# SFP.net
KiCad netlist of a schematic drawn in Altium Designer
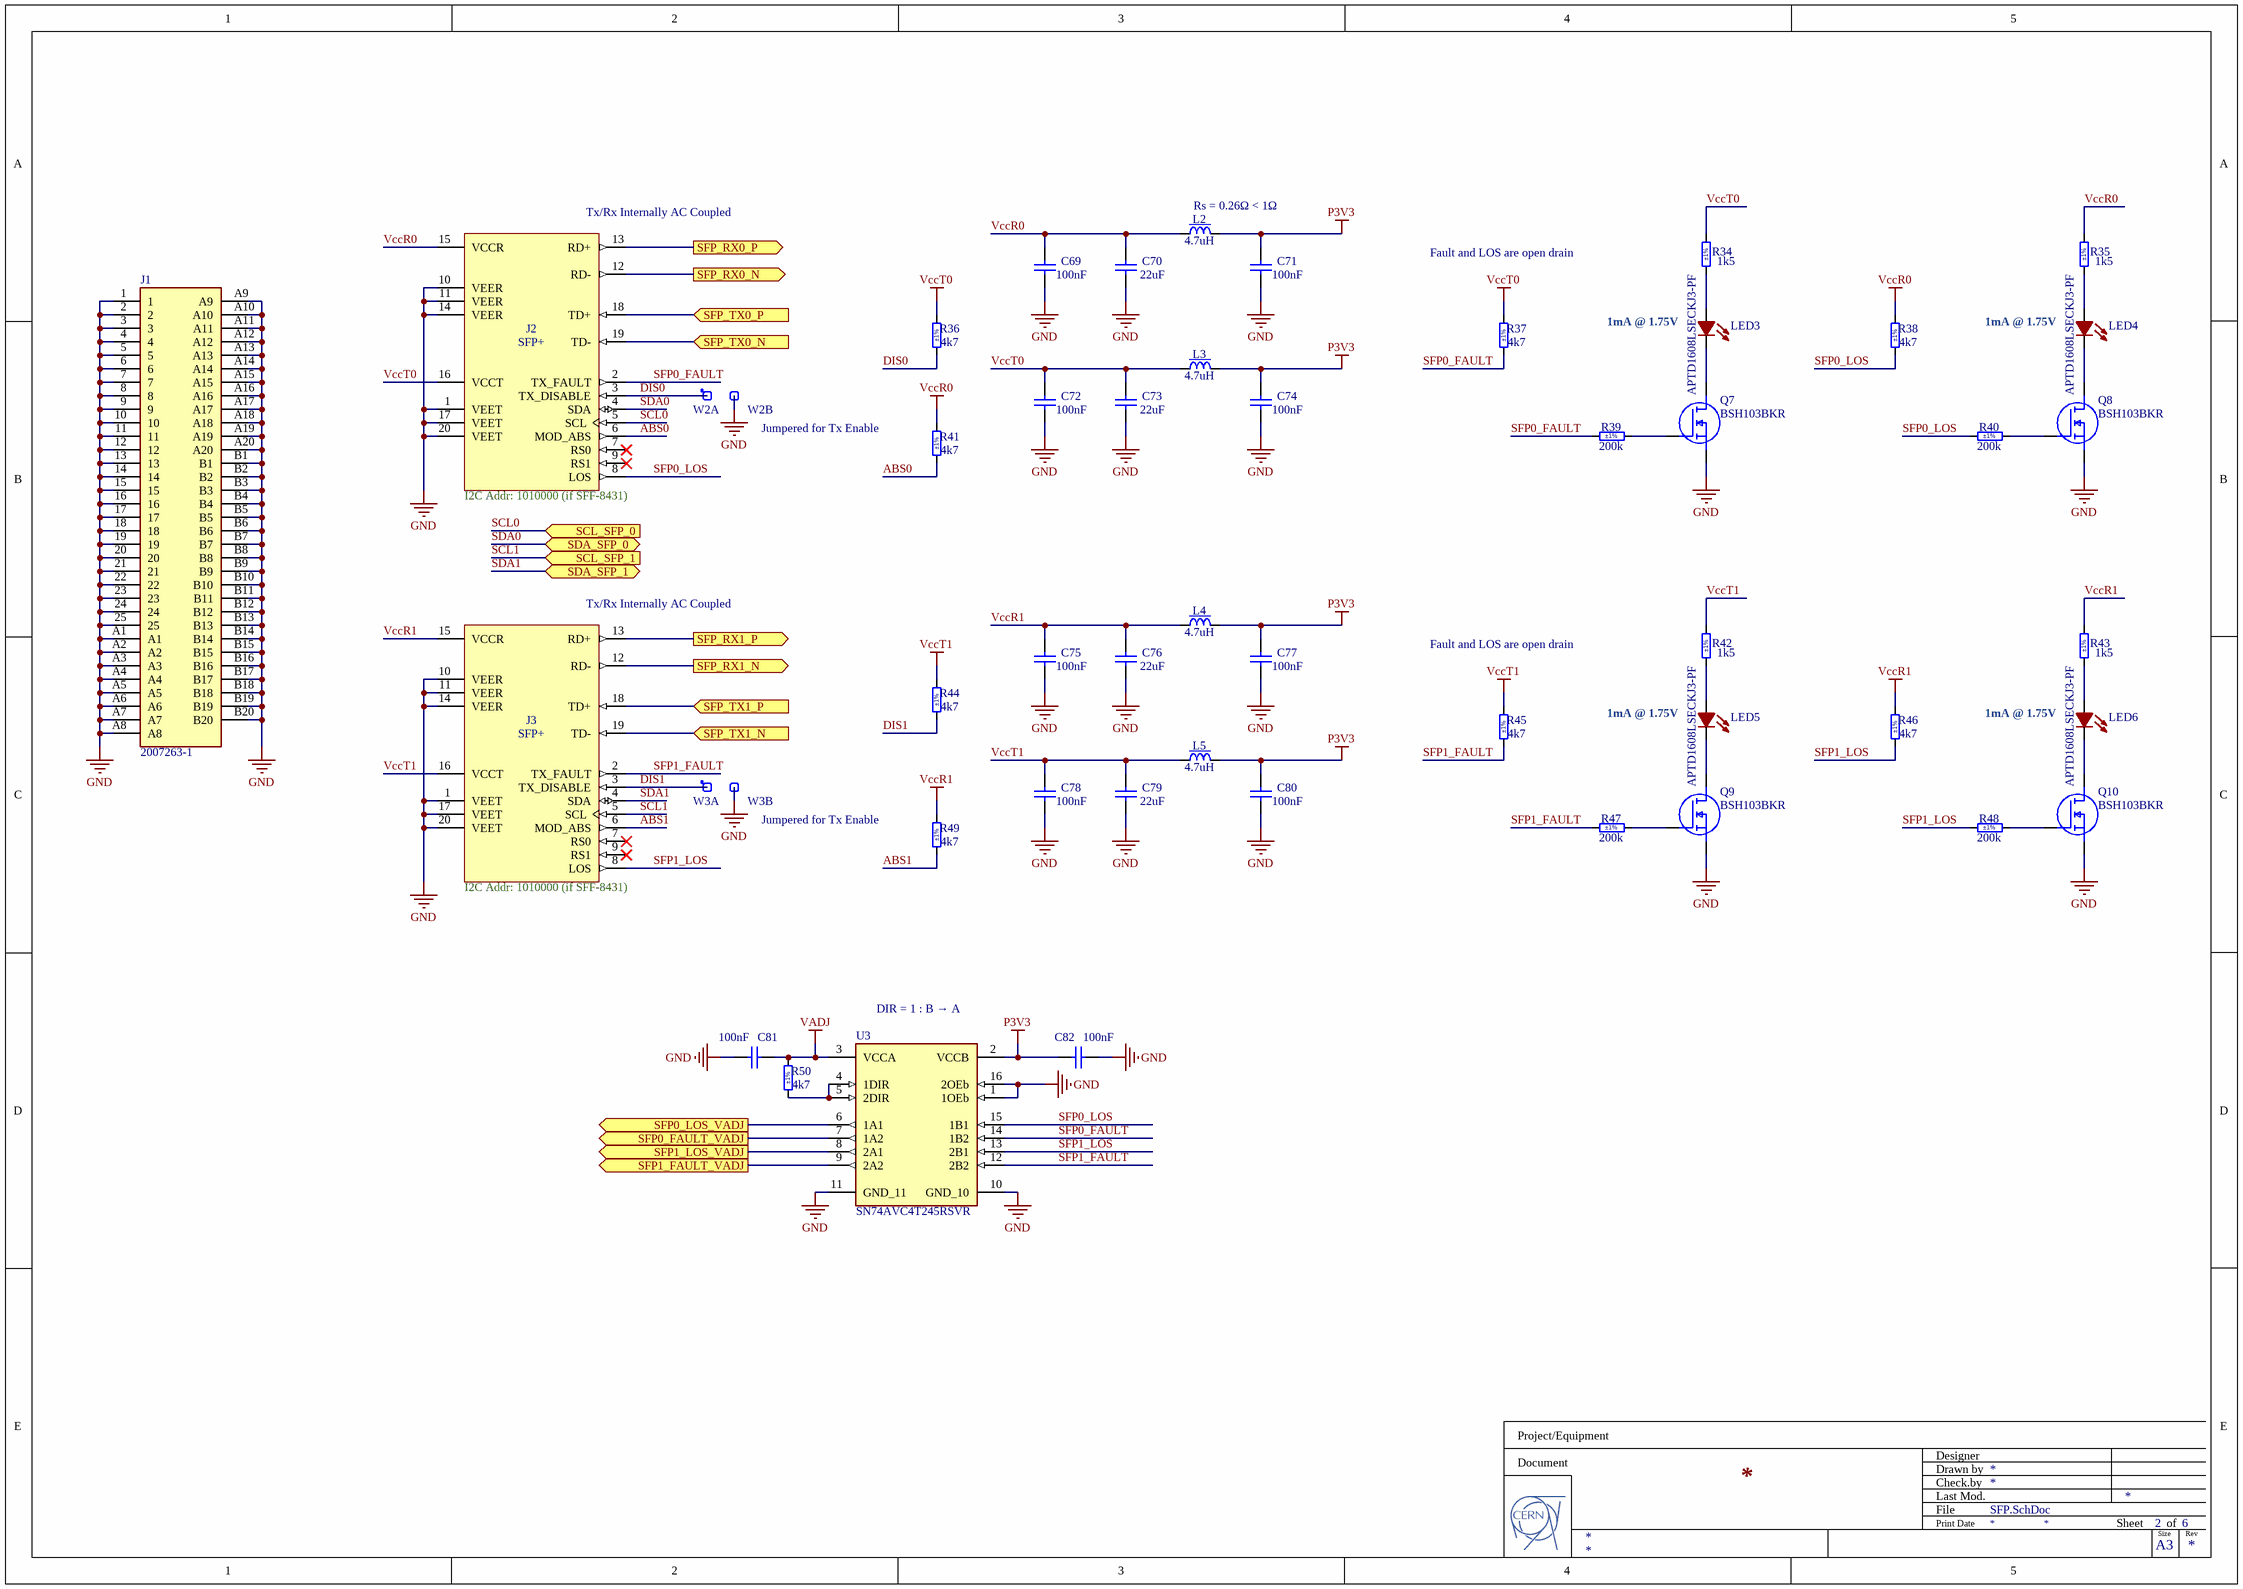
[diagram p0: SFP.SchDoc]

(export (version "E")
  (design (tool "Eeschema 10.0.6"))
  (components
    (comp (ref "C69")
      (value "100nF")
      (footprint "CAPC0603X33N")
      (description "Non-polarised capacitor")
      (fields
        (field (name "PART NUMBER") "CC0201_100NF_6.3V_10%_X7R")
        (field (name "VOLTAGE") "6.3V")
        (field (name "AUTHOR") "CERN DEM BC")
      )
      (libsource (lib "Capacitors") (part "Capacitor - non polarized"))
    )
    (comp (ref "C70")
      (value "22uF")
      (footprint "CAPC1005X70N")
      (description "GRM155R60J226ME11")
      (fields
        (field (name "PART NUMBER") "CC0402_10UF_6.3V_20%_X5R")
        (field (name "VOLTAGE") "6.3V")
        (field (name "AUTHOR") "CERN DEM JLC")
      )
      (libsource (lib "Capacitors") (part "Capacitor - non polarized"))
    )
    (comp (ref "C71")
      (value "100nF")
      (footprint "CAPC0603X33N")
      (description "Non-polarised capacitor")
      (fields
        (field (name "PART NUMBER") "CC0201_100NF_6.3V_10%_X7R")
        (field (name "VOLTAGE") "6.3V")
        (field (name "AUTHOR") "CERN DEM BC")
      )
      (libsource (lib "Capacitors") (part "Capacitor - non polarized"))
    )
    (comp (ref "C72")
      (value "100nF")
      (footprint "CAPC0603X33N")
      (description "Non-polarised capacitor")
      (fields
        (field (name "PART NUMBER") "CC0201_100NF_6.3V_10%_X7R")
        (field (name "VOLTAGE") "6.3V")
        (field (name "AUTHOR") "CERN DEM BC")
      )
      (libsource (lib "Capacitors") (part "Capacitor - non polarized"))
    )
    (comp (ref "C73")
      (value "22uF")
      (footprint "CAPC1005X70N")
      (description "GRM155R60J226ME11")
      (fields
        (field (name "PART NUMBER") "CC0402_10UF_6.3V_20%_X5R")
        (field (name "VOLTAGE") "6.3V")
        (field (name "AUTHOR") "CERN DEM JLC")
      )
      (libsource (lib "Capacitors") (part "Capacitor - non polarized"))
    )
    (comp (ref "C74")
      (value "100nF")
      (footprint "CAPC0603X33N")
      (description "Non-polarised capacitor")
      (fields
        (field (name "PART NUMBER") "CC0201_100NF_6.3V_10%_X7R")
        (field (name "VOLTAGE") "6.3V")
        (field (name "AUTHOR") "CERN DEM BC")
      )
      (libsource (lib "Capacitors") (part "Capacitor - non polarized"))
    )
    (comp (ref "C75")
      (value "100nF")
      (footprint "CAPC0603X33N")
      (description "Non-polarised capacitor")
      (fields
        (field (name "PART NUMBER") "CC0201_100NF_6.3V_10%_X7R")
        (field (name "VOLTAGE") "6.3V")
        (field (name "AUTHOR") "CERN DEM BC")
      )
      (libsource (lib "Capacitors") (part "Capacitor - non polarized"))
    )
    (comp (ref "C76")
      (value "22uF")
      (footprint "CAPC1005X70N")
      (description "GRM155R60J226ME11")
      (fields
        (field (name "PART NUMBER") "CC0402_10UF_6.3V_20%_X5R")
        (field (name "VOLTAGE") "6.3V")
        (field (name "AUTHOR") "CERN DEM JLC")
      )
      (libsource (lib "Capacitors") (part "Capacitor - non polarized"))
    )
    (comp (ref "C77")
      (value "100nF")
      (footprint "CAPC0603X33N")
      (description "Non-polarised capacitor")
      (fields
        (field (name "PART NUMBER") "CC0201_100NF_6.3V_10%_X7R")
        (field (name "VOLTAGE") "6.3V")
        (field (name "AUTHOR") "CERN DEM BC")
      )
      (libsource (lib "Capacitors") (part "Capacitor - non polarized"))
    )
    (comp (ref "C78")
      (value "100nF")
      (footprint "CAPC0603X33N")
      (description "Non-polarised capacitor")
      (fields
        (field (name "PART NUMBER") "CC0201_100NF_6.3V_10%_X7R")
        (field (name "VOLTAGE") "6.3V")
        (field (name "AUTHOR") "CERN DEM BC")
      )
      (libsource (lib "Capacitors") (part "Capacitor - non polarized"))
    )
    (comp (ref "C79")
      (value "22uF")
      (footprint "CAPC1005X70N")
      (description "GRM155R60J226ME11")
      (fields
        (field (name "PART NUMBER") "CC0402_10UF_6.3V_20%_X5R")
        (field (name "VOLTAGE") "6.3V")
        (field (name "AUTHOR") "CERN DEM JLC")
      )
      (libsource (lib "Capacitors") (part "Capacitor - non polarized"))
    )
    (comp (ref "C80")
      (value "100nF")
      (footprint "CAPC0603X33N")
      (description "Non-polarised capacitor")
      (fields
        (field (name "PART NUMBER") "CC0201_100NF_6.3V_10%_X7R")
        (field (name "VOLTAGE") "6.3V")
        (field (name "AUTHOR") "CERN DEM BC")
      )
      (libsource (lib "Capacitors") (part "Capacitor - non polarized"))
    )
    (comp (ref "C81")
      (value "100nF")
      (footprint "CAPC0603X33N")
      (description "GRM033R61C104KE14")
      (fields
        (field (name "PART NUMBER") "CC0201_100NF_6.3V_10%_X5R")
        (field (name "VOLTAGE") "6.3V")
        (field (name "AUTHOR") "CERN DEM JLC")
      )
      (libsource (lib "Capacitors") (part "Capacitor - non polarized"))
    )
    (comp (ref "C82")
      (value "100nF")
      (footprint "CAPC0603X33N")
      (description "GRM033R61C104KE14")
      (fields
        (field (name "PART NUMBER") "CC0201_100NF_6.3V_10%_X5R")
        (field (name "VOLTAGE") "6.3V")
        (field (name "AUTHOR") "CERN DEM JLC")
      )
      (libsource (lib "Capacitors") (part "Capacitor - non polarized"))
    )
    (comp (ref "J1")
      (value "2007263-1")
      (footprint "SamacSys:20072631")
      (description "Connector")
      (fields (field (name "MOUSER PART NUMBER") "571-2007263-1"))
      (libsource (lib "SamacSys") (part "2007263-1"))
    )
    (comp (ref "J2")
      (value "SFP+")
      (footprint "TYCO_1888247-1")
      (description "20 Position SFP+ Connector (Small Form-factor Pluggable)")
      (fields
        (field (name "PART NUMBER") "TYCO_1888247-1")
        (field (name "MANUFACTURER") "TYCO ELECTRONICS")
        (field (name "AUTHOR") "CERN DEM JLC")
      )
      (libsource (lib "Connectors") (part "SFP+x1"))
    )
    (comp (ref "J3")
      (value "SFP+")
      (footprint "TYCO_1888247-1")
      (description "20 Position SFP+ Connector (Small Form-factor Pluggable)")
      (fields
        (field (name "PART NUMBER") "TYCO_1888247-1")
        (field (name "MANUFACTURER") "TYCO ELECTRONICS")
        (field (name "AUTHOR") "CERN DEM JLC")
      )
      (libsource (lib "Connectors") (part "SFP+x1"))
    )
    (comp (ref "L2")
      (value "4.7uH")
      (footprint "IND_MURATA_LQH32C")
      (description "Inductor With Core. Rs = 0.26Ω < 1Ω")
      (fields
        (field (name "PART NUMBER") "IND_4.7UH_20%_MURATA_LQH32CN4R7M23L")
        (field (name "POWER") "450mA")
        (field (name "AUTHOR") "CERN DEM JLC")
      )
      (libsource (lib "Inductors & Transformers") (part "Inductor With Magnetic core"))
    )
    (comp (ref "L3")
      (value "4.7uH")
      (footprint "IND_MURATA_LQH32C")
      (description "Inductor With Core. Rs = 0.26Ω < 1Ω")
      (fields
        (field (name "PART NUMBER") "IND_4.7UH_20%_MURATA_LQH32CN4R7M23L")
        (field (name "POWER") "450mA")
        (field (name "AUTHOR") "CERN DEM JLC")
      )
      (libsource (lib "Inductors & Transformers") (part "Inductor With Magnetic core"))
    )
    (comp (ref "L4")
      (value "4.7uH")
      (footprint "IND_MURATA_LQH32C")
      (description "Inductor With Core. Rs = 0.26Ω < 1Ω")
      (fields
        (field (name "PART NUMBER") "IND_4.7UH_20%_MURATA_LQH32CN4R7M23L")
        (field (name "POWER") "450mA")
        (field (name "AUTHOR") "CERN DEM JLC")
      )
      (libsource (lib "Inductors & Transformers") (part "Inductor With Magnetic core"))
    )
    (comp (ref "L5")
      (value "4.7uH")
      (footprint "IND_MURATA_LQH32C")
      (description "Inductor With Core. Rs = 0.26Ω < 1Ω")
      (fields
        (field (name "PART NUMBER") "IND_4.7UH_20%_MURATA_LQH32CN4R7M23L")
        (field (name "POWER") "450mA")
        (field (name "AUTHOR") "CERN DEM JLC")
      )
      (libsource (lib "Inductors & Transformers") (part "Inductor With Magnetic core"))
    )
    (comp (ref "LED3")
      (value "APTD1608LSECKJ3-PF")
      (footprint "APTD1608LSECKJ3-PF:LED_APTD1608LSECKJ3-PF_KNB")
      (description "Led Red 0603 2mA 1.8V 50mcd 84mW")
      (libsource (lib "APTD1608LSECKJ3-PF") (part "APTD1608LSECKJ3-PF"))
    )
    (comp (ref "LED4")
      (value "APTD1608LSECKJ3-PF")
      (footprint "APTD1608LSECKJ3-PF:LED_APTD1608LSECKJ3-PF_KNB")
      (description "Led Red 0603 2mA 1.8V 50mcd 84mW")
      (libsource (lib "APTD1608LSECKJ3-PF") (part "APTD1608LSECKJ3-PF"))
    )
    (comp (ref "LED5")
      (value "APTD1608LSECKJ3-PF")
      (footprint "APTD1608LSECKJ3-PF:LED_APTD1608LSECKJ3-PF_KNB")
      (description "Led Red 0603 2mA 1.8V 50mcd 84mW")
      (libsource (lib "APTD1608LSECKJ3-PF") (part "APTD1608LSECKJ3-PF"))
    )
    (comp (ref "LED6")
      (value "APTD1608LSECKJ3-PF")
      (footprint "APTD1608LSECKJ3-PF:LED_APTD1608LSECKJ3-PF_KNB")
      (description "Led Red 0603 2mA 1.8V 50mcd 84mW")
      (libsource (lib "APTD1608LSECKJ3-PF") (part "APTD1608LSECKJ3-PF"))
    )
    (comp (ref "Q7")
      (value "BSH103BKR")
      (footprint "SamacSys:SOT95P230X110-3N")
      (description "MOSFET (N-Channel)")
      (fields (field (name "MOUSER PART NUMBER") "771-BSH103BKR"))
      (libsource (lib "SamacSys") (part "BSH103BKR"))
    )
    (comp (ref "Q8")
      (value "BSH103BKR")
      (footprint "SamacSys:SOT95P230X110-3N")
      (description "MOSFET (N-Channel)")
      (fields (field (name "MOUSER PART NUMBER") "771-BSH103BKR"))
      (libsource (lib "SamacSys") (part "BSH103BKR"))
    )
    (comp (ref "Q9")
      (value "BSH103BKR")
      (footprint "SamacSys:SOT95P230X110-3N")
      (description "MOSFET (N-Channel)")
      (fields (field (name "MOUSER PART NUMBER") "771-BSH103BKR"))
      (libsource (lib "SamacSys") (part "BSH103BKR"))
    )
    (comp (ref "Q10")
      (value "BSH103BKR")
      (footprint "SamacSys:SOT95P230X110-3N")
      (description "MOSFET (N-Channel)")
      (fields (field (name "MOUSER PART NUMBER") "771-BSH103BKR"))
      (libsource (lib "SamacSys") (part "BSH103BKR"))
    )
    (comp (ref "R34")
      (value "1k5")
      (footprint "RESC1005X40N")
      (description "Resistor - 1%")
      (fields
        (field (name "TOLERANCE") "±1%")
        (field (name "PART NUMBER") "R0402_1K5_1%_0.0625W_100PPM")
        (field (name "POWER") "0.0625W")
        (field (name "AUTHOR") "CERN DEM JLC")
      )
      (libsource (lib "Resistors") (part "Resistor - 1%"))
    )
    (comp (ref "R35")
      (value "1k5")
      (footprint "RESC1005X40N")
      (description "Resistor - 1%")
      (fields
        (field (name "TOLERANCE") "±1%")
        (field (name "PART NUMBER") "R0402_1K5_1%_0.0625W_100PPM")
        (field (name "POWER") "0.0625W")
        (field (name "AUTHOR") "CERN DEM JLC")
      )
      (libsource (lib "Resistors") (part "Resistor - 1%"))
    )
    (comp (ref "R36")
      (value "4k7")
      (footprint "RESC1005X40N")
      (description "Resistor - 1%")
      (fields
        (field (name "TOLERANCE") "±1%")
        (field (name "PART NUMBER") "R0402_4K7_1%_0.0625W_100PPM")
        (field (name "POWER") "0.0625W")
        (field (name "AUTHOR") "CERN DEM JLC")
      )
      (libsource (lib "Resistors") (part "Resistor - 1%"))
    )
    (comp (ref "R37")
      (value "4k7")
      (footprint "RESC1005X40N")
      (description "Resistor - 1%")
      (fields
        (field (name "TOLERANCE") "±1%")
        (field (name "PART NUMBER") "R0402_4K7_1%_0.0625W_100PPM")
        (field (name "POWER") "0.0625W")
        (field (name "AUTHOR") "CERN DEM JLC")
      )
      (libsource (lib "Resistors") (part "Resistor - 1%"))
    )
    (comp (ref "R38")
      (value "4k7")
      (footprint "RESC1005X40N")
      (description "Resistor - 1%")
      (fields
        (field (name "TOLERANCE") "±1%")
        (field (name "PART NUMBER") "R0402_4K7_1%_0.0625W_100PPM")
        (field (name "POWER") "0.0625W")
        (field (name "AUTHOR") "CERN DEM JLC")
      )
      (libsource (lib "Resistors") (part "Resistor - 1%"))
    )
    (comp (ref "R39")
      (value "200k")
      (footprint "RESC1005X40N")
      (description "Resistor - 1%")
      (fields
        (field (name "TOLERANCE") "±1%")
        (field (name "PART NUMBER") "R0402_200K_1%_0.0625W_100PPM")
        (field (name "POWER") "0.0625W")
        (field (name "AUTHOR") "CERN DEM JLC")
      )
      (libsource (lib "Resistors") (part "Resistor - 1%"))
    )
    (comp (ref "R40")
      (value "200k")
      (footprint "RESC1005X40N")
      (description "Resistor - 1%")
      (fields
        (field (name "TOLERANCE") "±1%")
        (field (name "PART NUMBER") "R0402_200K_1%_0.0625W_100PPM")
        (field (name "POWER") "0.0625W")
        (field (name "AUTHOR") "CERN DEM JLC")
      )
      (libsource (lib "Resistors") (part "Resistor - 1%"))
    )
    (comp (ref "R41")
      (value "4k7")
      (footprint "RESC1005X40N")
      (description "Resistor - 1%")
      (fields
        (field (name "TOLERANCE") "±1%")
        (field (name "PART NUMBER") "R0402_4K7_1%_0.0625W_100PPM")
        (field (name "POWER") "0.0625W")
        (field (name "AUTHOR") "CERN DEM JLC")
      )
      (libsource (lib "Resistors") (part "Resistor - 1%"))
    )
    (comp (ref "R42")
      (value "1k5")
      (footprint "RESC1005X40N")
      (description "Resistor - 1%")
      (fields
        (field (name "TOLERANCE") "±1%")
        (field (name "PART NUMBER") "R0402_1K5_1%_0.0625W_100PPM")
        (field (name "POWER") "0.0625W")
        (field (name "AUTHOR") "CERN DEM JLC")
      )
      (libsource (lib "Resistors") (part "Resistor - 1%"))
    )
    (comp (ref "R43")
      (value "1k5")
      (footprint "RESC1005X40N")
      (description "Resistor - 1%")
      (fields
        (field (name "TOLERANCE") "±1%")
        (field (name "PART NUMBER") "R0402_1K5_1%_0.0625W_100PPM")
        (field (name "POWER") "0.0625W")
        (field (name "AUTHOR") "CERN DEM JLC")
      )
      (libsource (lib "Resistors") (part "Resistor - 1%"))
    )
    (comp (ref "R44")
      (value "4k7")
      (footprint "RESC1005X40N")
      (description "Resistor - 1%")
      (fields
        (field (name "TOLERANCE") "±1%")
        (field (name "PART NUMBER") "R0402_4K7_1%_0.0625W_100PPM")
        (field (name "POWER") "0.0625W")
        (field (name "AUTHOR") "CERN DEM JLC")
      )
      (libsource (lib "Resistors") (part "Resistor - 1%"))
    )
    (comp (ref "R45")
      (value "4k7")
      (footprint "RESC1005X40N")
      (description "Resistor - 1%")
      (fields
        (field (name "TOLERANCE") "±1%")
        (field (name "PART NUMBER") "R0402_4K7_1%_0.0625W_100PPM")
        (field (name "POWER") "0.0625W")
        (field (name "AUTHOR") "CERN DEM JLC")
      )
      (libsource (lib "Resistors") (part "Resistor - 1%"))
    )
    (comp (ref "R46")
      (value "4k7")
      (footprint "RESC1005X40N")
      (description "Resistor - 1%")
      (fields
        (field (name "TOLERANCE") "±1%")
        (field (name "PART NUMBER") "R0402_4K7_1%_0.0625W_100PPM")
        (field (name "POWER") "0.0625W")
        (field (name "AUTHOR") "CERN DEM JLC")
      )
      (libsource (lib "Resistors") (part "Resistor - 1%"))
    )
    (comp (ref "R47")
      (value "200k")
      (footprint "RESC1005X40N")
      (description "Resistor - 1%")
      (fields
        (field (name "TOLERANCE") "±1%")
        (field (name "PART NUMBER") "R0402_200K_1%_0.0625W_100PPM")
        (field (name "POWER") "0.0625W")
        (field (name "AUTHOR") "CERN DEM JLC")
      )
      (libsource (lib "Resistors") (part "Resistor - 1%"))
    )
    (comp (ref "R48")
      (value "200k")
      (footprint "RESC1005X40N")
      (description "Resistor - 1%")
      (fields
        (field (name "TOLERANCE") "±1%")
        (field (name "PART NUMBER") "R0402_200K_1%_0.0625W_100PPM")
        (field (name "POWER") "0.0625W")
        (field (name "AUTHOR") "CERN DEM JLC")
      )
      (libsource (lib "Resistors") (part "Resistor - 1%"))
    )
    (comp (ref "R49")
      (value "4k7")
      (footprint "RESC1005X40N")
      (description "Resistor - 1%")
      (fields
        (field (name "TOLERANCE") "±1%")
        (field (name "PART NUMBER") "R0402_4K7_1%_0.0625W_100PPM")
        (field (name "POWER") "0.0625W")
        (field (name "AUTHOR") "CERN DEM JLC")
      )
      (libsource (lib "Resistors") (part "Resistor - 1%"))
    )
    (comp (ref "R50")
      (value "4k7")
      (footprint "RESC1005X40N")
      (description "Resistor - 1%")
      (fields
        (field (name "TOLERANCE") "±1%")
        (field (name "PART NUMBER") "R0402_4K7_1%_0.0625W_100PPM")
        (field (name "POWER") "0.0625W")
        (field (name "AUTHOR") "CERN DEM JLC")
      )
      (libsource (lib "Resistors") (part "Resistor - 1%"))
    )
    (comp (ref "U3")
      (value "SN74AVC4T245RSVR")
      (footprint "QFN40P260X180X55-16N:QFN40P260X180X55-16N")
      (fields (field (name "MF") "Texas Instruments"))
      (libsource (lib "SN74AVC4T245RSVR") (part "SN74AVC4T245RSVR"))
    )
    (comp (ref "W2")
      (value "Header 2")
      (footprint "SAMTEC_HTSW-102-23-L-S")
      (description "2 Mini Wire-Wrap Contact Strip Header")
      (fields
        (field (name "PART NUMBER") "SAMTEC_HTSW-102-23-L-S")
        (field (name "MANUFACTURER") "SAMTEC")
        (field (name "AUTHOR") "CERN DEM JLC")
      )
      (libsource (lib "Connectors") (part "Wire-Wrap Contact x2"))
    )
    (comp (ref "W3")
      (value "Header 2")
      (footprint "SAMTEC_HTSW-102-23-L-S")
      (description "2 Mini Wire-Wrap Contact Strip Header")
      (fields
        (field (name "PART NUMBER") "SAMTEC_HTSW-102-23-L-S")
        (field (name "MANUFACTURER") "SAMTEC")
        (field (name "AUTHOR") "CERN DEM JLC")
      )
      (libsource (lib "Connectors") (part "Wire-Wrap Contact x2"))
    )
  )
  (nets
    (net (code "1") (name "/ABS0") (class "Default")
      (node (ref "J2") (pin "6") (pinfunction "MOD_ABS_6") (pintype "output"))
      (node (ref "R41") (pin "1") (pinfunction "1_1") (pintype "passive"))
    )
    (net (code "2") (name "/ABS1") (class "Default")
      (node (ref "J3") (pin "6") (pinfunction "MOD_ABS_6") (pintype "output"))
      (node (ref "R49") (pin "1") (pinfunction "1_1") (pintype "passive"))
    )
    (net (code "3") (name "/DIS0") (class "Default")
      (node (ref "J2") (pin "3") (pinfunction "TX_DISABLE_3") (pintype "input"))
      (node (ref "R36") (pin "1") (pinfunction "1_1") (pintype "passive"))
      (node (ref "W2") (pin "1") (pinfunction "1_1") (pintype "passive"))
    )
    (net (code "4") (name "/DIS1") (class "Default")
      (node (ref "J3") (pin "3") (pinfunction "TX_DISABLE_3") (pintype "input"))
      (node (ref "R44") (pin "1") (pinfunction "1_1") (pintype "passive"))
      (node (ref "W3") (pin "1") (pinfunction "1_1") (pintype "passive"))
    )
    (net (code "5") (name "/SCL0") (class "Default")
      (node (ref "J2") (pin "5") (pinfunction "SCL_5") (pintype "input"))
    )
    (net (code "6") (name "/SCL1") (class "Default")
      (node (ref "J3") (pin "5") (pinfunction "SCL_5") (pintype "input"))
    )
    (net (code "7") (name "/SDA0") (class "Default")
      (node (ref "J2") (pin "4") (pinfunction "SDA_4") (pintype "bidirectional"))
    )
    (net (code "8") (name "/SDA1") (class "Default")
      (node (ref "J3") (pin "4") (pinfunction "SDA_4") (pintype "bidirectional"))
    )
    (net (code "9") (name "/SFP0_FAULT") (class "Default")
      (node (ref "J2") (pin "2") (pinfunction "TX_FAULT_2") (pintype "output"))
      (node (ref "R37") (pin "1") (pinfunction "1_1") (pintype "passive"))
      (node (ref "R39") (pin "1") (pinfunction "1_1") (pintype "passive"))
      (node (ref "U3") (pin "14") (pinfunction "1B2_14") (pintype "input"))
    )
    (net (code "10") (name "/SFP0_FAULT_VADJ") (class "Default")
      (node (ref "U3") (pin "7") (pinfunction "1A2_7") (pintype "output"))
    )
    (net (code "11") (name "/SFP0_LOS") (class "Default")
      (node (ref "J2") (pin "8") (pinfunction "LOS_8") (pintype "output"))
      (node (ref "R38") (pin "1") (pinfunction "1_1") (pintype "passive"))
      (node (ref "R40") (pin "1") (pinfunction "1_1") (pintype "passive"))
      (node (ref "U3") (pin "15") (pinfunction "1B1_15") (pintype "input"))
    )
    (net (code "12") (name "/SFP0_LOS_VADJ") (class "Default")
      (node (ref "U3") (pin "6") (pinfunction "1A1_6") (pintype "output"))
    )
    (net (code "13") (name "/SFP1_FAULT") (class "Default")
      (node (ref "J3") (pin "2") (pinfunction "TX_FAULT_2") (pintype "output"))
      (node (ref "R45") (pin "1") (pinfunction "1_1") (pintype "passive"))
      (node (ref "R47") (pin "1") (pinfunction "1_1") (pintype "passive"))
      (node (ref "U3") (pin "12") (pinfunction "2B2_12") (pintype "input"))
    )
    (net (code "14") (name "/SFP1_FAULT_VADJ") (class "Default")
      (node (ref "U3") (pin "9") (pinfunction "2A2_9") (pintype "output"))
    )
    (net (code "15") (name "/SFP1_LOS") (class "Default")
      (node (ref "J3") (pin "8") (pinfunction "LOS_8") (pintype "output"))
      (node (ref "R46") (pin "1") (pinfunction "1_1") (pintype "passive"))
      (node (ref "R48") (pin "1") (pinfunction "1_1") (pintype "passive"))
      (node (ref "U3") (pin "13") (pinfunction "2B1_13") (pintype "input"))
    )
    (net (code "16") (name "/SFP1_LOS_VADJ") (class "Default")
      (node (ref "U3") (pin "8") (pinfunction "2A1_8") (pintype "output"))
    )
    (net (code "17") (name "/SFP_RX0_N") (class "Default")
      (node (ref "J2") (pin "12") (pinfunction "RD-_12") (pintype "output"))
    )
    (net (code "18") (name "/SFP_RX0_P") (class "Default")
      (node (ref "J2") (pin "13") (pinfunction "RD+_13") (pintype "output"))
    )
    (net (code "19") (name "/SFP_RX1_N") (class "Default")
      (node (ref "J3") (pin "12") (pinfunction "RD-_12") (pintype "output"))
    )
    (net (code "20") (name "/SFP_RX1_P") (class "Default")
      (node (ref "J3") (pin "13") (pinfunction "RD+_13") (pintype "output"))
    )
    (net (code "21") (name "/SFP_TX0_N") (class "Default")
      (node (ref "J2") (pin "19") (pinfunction "TD-_19") (pintype "input"))
    )
    (net (code "22") (name "/SFP_TX0_P") (class "Default")
      (node (ref "J2") (pin "18") (pinfunction "TD+_18") (pintype "input"))
    )
    (net (code "23") (name "/SFP_TX1_N") (class "Default")
      (node (ref "J3") (pin "19") (pinfunction "TD-_19") (pintype "input"))
    )
    (net (code "24") (name "/SFP_TX1_P") (class "Default")
      (node (ref "J3") (pin "18") (pinfunction "TD+_18") (pintype "input"))
    )
    (net (code "25") (name "GND") (class "Default")
      (node (ref "C69") (pin "1") (pinfunction "1_1") (pintype "passive"))
      (node (ref "C70") (pin "1") (pinfunction "1_1") (pintype "passive"))
      (node (ref "C71") (pin "1") (pinfunction "1_1") (pintype "passive"))
      (node (ref "C72") (pin "1") (pinfunction "1_1") (pintype "passive"))
      (node (ref "C73") (pin "1") (pinfunction "1_1") (pintype "passive"))
      (node (ref "C74") (pin "1") (pinfunction "1_1") (pintype "passive"))
      (node (ref "C75") (pin "1") (pinfunction "1_1") (pintype "passive"))
      (node (ref "C76") (pin "1") (pinfunction "1_1") (pintype "passive"))
      (node (ref "C77") (pin "1") (pinfunction "1_1") (pintype "passive"))
      (node (ref "C78") (pin "1") (pinfunction "1_1") (pintype "passive"))
      (node (ref "C79") (pin "1") (pinfunction "1_1") (pintype "passive"))
      (node (ref "C80") (pin "1") (pinfunction "1_1") (pintype "passive"))
      (node (ref "C81") (pin "1") (pinfunction "1_1") (pintype "passive"))
      (node (ref "C82") (pin "1") (pinfunction "1_1") (pintype "passive"))
      (node (ref "J1") (pin "1") (pinfunction "1_1") (pintype "passive"))
      (node (ref "J1") (pin "10") (pinfunction "10_10") (pintype "passive"))
      (node (ref "J1") (pin "11") (pinfunction "11_11") (pintype "passive"))
      (node (ref "J1") (pin "12") (pinfunction "12_12") (pintype "passive"))
      (node (ref "J1") (pin "13") (pinfunction "13_13") (pintype "passive"))
      (node (ref "J1") (pin "14") (pinfunction "14_14") (pintype "passive"))
      (node (ref "J1") (pin "15") (pinfunction "15_15") (pintype "passive"))
      (node (ref "J1") (pin "16") (pinfunction "16_16") (pintype "passive"))
      (node (ref "J1") (pin "17") (pinfunction "17_17") (pintype "passive"))
      (node (ref "J1") (pin "18") (pinfunction "18_18") (pintype "passive"))
      (node (ref "J1") (pin "19") (pinfunction "19_19") (pintype "passive"))
      (node (ref "J1") (pin "2") (pinfunction "2_2") (pintype "passive"))
      (node (ref "J1") (pin "20") (pinfunction "20_20") (pintype "passive"))
      (node (ref "J1") (pin "21") (pinfunction "21_21") (pintype "passive"))
      (node (ref "J1") (pin "22") (pinfunction "22_22") (pintype "passive"))
      (node (ref "J1") (pin "23") (pinfunction "23_23") (pintype "passive"))
      (node (ref "J1") (pin "24") (pinfunction "24_24") (pintype "passive"))
      (node (ref "J1") (pin "25") (pinfunction "25_25") (pintype "passive"))
      (node (ref "J1") (pin "3") (pinfunction "3_3") (pintype "passive"))
      (node (ref "J1") (pin "4") (pinfunction "4_4") (pintype "passive"))
      (node (ref "J1") (pin "5") (pinfunction "5_5") (pintype "passive"))
      (node (ref "J1") (pin "6") (pinfunction "6_6") (pintype "passive"))
      (node (ref "J1") (pin "7") (pinfunction "7_7") (pintype "passive"))
      (node (ref "J1") (pin "8") (pinfunction "8_8") (pintype "passive"))
      (node (ref "J1") (pin "9") (pinfunction "9_9") (pintype "passive"))
      (node (ref "J1") (pin "A1") (pinfunction "A1_A1") (pintype "passive"))
      (node (ref "J1") (pin "A10") (pinfunction "A10_A10") (pintype "passive"))
      (node (ref "J1") (pin "A11") (pinfunction "A11_A11") (pintype "passive"))
      (node (ref "J1") (pin "A12") (pinfunction "A12_A12") (pintype "passive"))
      (node (ref "J1") (pin "A13") (pinfunction "A13_A13") (pintype "passive"))
      (node (ref "J1") (pin "A14") (pinfunction "A14_A14") (pintype "passive"))
      (node (ref "J1") (pin "A15") (pinfunction "A15_A15") (pintype "passive"))
      (node (ref "J1") (pin "A16") (pinfunction "A16_A16") (pintype "passive"))
      (node (ref "J1") (pin "A17") (pinfunction "A17_A17") (pintype "passive"))
      (node (ref "J1") (pin "A18") (pinfunction "A18_A18") (pintype "passive"))
      (node (ref "J1") (pin "A19") (pinfunction "A19_A19") (pintype "passive"))
      (node (ref "J1") (pin "A2") (pinfunction "A2_A2") (pintype "passive"))
      (node (ref "J1") (pin "A20") (pinfunction "A20_A20") (pintype "passive"))
      (node (ref "J1") (pin "A3") (pinfunction "A3_A3") (pintype "passive"))
      (node (ref "J1") (pin "A4") (pinfunction "A4_A4") (pintype "passive"))
      (node (ref "J1") (pin "A5") (pinfunction "A5_A5") (pintype "passive"))
      (node (ref "J1") (pin "A6") (pinfunction "A6_A6") (pintype "passive"))
      (node (ref "J1") (pin "A7") (pinfunction "A7_A7") (pintype "passive"))
      (node (ref "J1") (pin "A8") (pinfunction "A8_A8") (pintype "passive"))
      (node (ref "J1") (pin "A9") (pinfunction "A9_A9") (pintype "passive"))
      (node (ref "J1") (pin "B1") (pinfunction "B1_B1") (pintype "passive"))
      (node (ref "J1") (pin "B10") (pinfunction "B10_B10") (pintype "passive"))
      (node (ref "J1") (pin "B11") (pinfunction "B11_B11") (pintype "passive"))
      (node (ref "J1") (pin "B12") (pinfunction "B12_B12") (pintype "passive"))
      (node (ref "J1") (pin "B13") (pinfunction "B13_B13") (pintype "passive"))
      (node (ref "J1") (pin "B14") (pinfunction "B14_B14") (pintype "passive"))
      (node (ref "J1") (pin "B15") (pinfunction "B15_B15") (pintype "passive"))
      (node (ref "J1") (pin "B16") (pinfunction "B16_B16") (pintype "passive"))
      (node (ref "J1") (pin "B17") (pinfunction "B17_B17") (pintype "passive"))
      (node (ref "J1") (pin "B18") (pinfunction "B18_B18") (pintype "passive"))
      (node (ref "J1") (pin "B19") (pinfunction "B19_B19") (pintype "passive"))
      (node (ref "J1") (pin "B2") (pinfunction "B2_B2") (pintype "passive"))
      (node (ref "J1") (pin "B20") (pinfunction "B20_B20") (pintype "passive"))
      (node (ref "J1") (pin "B3") (pinfunction "B3_B3") (pintype "passive"))
      (node (ref "J1") (pin "B4") (pinfunction "B4_B4") (pintype "passive"))
      (node (ref "J1") (pin "B5") (pinfunction "B5_B5") (pintype "passive"))
      (node (ref "J1") (pin "B6") (pinfunction "B6_B6") (pintype "passive"))
      (node (ref "J1") (pin "B7") (pinfunction "B7_B7") (pintype "passive"))
      (node (ref "J1") (pin "B8") (pinfunction "B8_B8") (pintype "passive"))
      (node (ref "J1") (pin "B9") (pinfunction "B9_B9") (pintype "passive"))
      (node (ref "J2") (pin "1") (pinfunction "VEET_1") (pintype "power_in"))
      (node (ref "J2") (pin "10") (pinfunction "VEER_10") (pintype "power_in"))
      (node (ref "J2") (pin "11") (pinfunction "VEER_11") (pintype "power_in"))
      (node (ref "J2") (pin "14") (pinfunction "VEER_14") (pintype "power_in"))
      (node (ref "J2") (pin "17") (pinfunction "VEET_17") (pintype "power_in"))
      (node (ref "J2") (pin "20") (pinfunction "VEET_20") (pintype "power_in"))
      (node (ref "J3") (pin "1") (pinfunction "VEET_1") (pintype "power_in"))
      (node (ref "J3") (pin "10") (pinfunction "VEER_10") (pintype "power_in"))
      (node (ref "J3") (pin "11") (pinfunction "VEER_11") (pintype "power_in"))
      (node (ref "J3") (pin "14") (pinfunction "VEER_14") (pintype "power_in"))
      (node (ref "J3") (pin "17") (pinfunction "VEET_17") (pintype "power_in"))
      (node (ref "J3") (pin "20") (pinfunction "VEET_20") (pintype "power_in"))
      (node (ref "Q10") (pin "2") (pinfunction "S_2") (pintype "passive"))
      (node (ref "Q7") (pin "2") (pinfunction "S_2") (pintype "passive"))
      (node (ref "Q8") (pin "2") (pinfunction "S_2") (pintype "passive"))
      (node (ref "Q9") (pin "2") (pinfunction "S_2") (pintype "passive"))
      (node (ref "U3") (pin "1") (pinfunction "1OEb_1") (pintype "input"))
      (node (ref "U3") (pin "10") (pinfunction "GND_10_10") (pintype "power_in"))
      (node (ref "U3") (pin "11") (pinfunction "GND_11_11") (pintype "power_in"))
      (node (ref "U3") (pin "16") (pinfunction "2OEb_16") (pintype "input"))
      (node (ref "W2") (pin "2") (pinfunction "2_2") (pintype "bidirectional"))
      (node (ref "W3") (pin "2") (pinfunction "2_2") (pintype "bidirectional"))
    )
    (net (code "26") (name "Net-(LED3-A)") (class "Default")
      (node (ref "LED3") (pin "2") (pinfunction "A_2") (pintype "passive"))
      (node (ref "R34") (pin "1") (pinfunction "1_1") (pintype "passive"))
    )
    (net (code "27") (name "Net-(LED3-C)") (class "Default")
      (node (ref "LED3") (pin "1") (pinfunction "C_1") (pintype "passive"))
      (node (ref "Q7") (pin "3") (pinfunction "D_3") (pintype "passive"))
    )
    (net (code "28") (name "Net-(LED4-A)") (class "Default")
      (node (ref "LED4") (pin "2") (pinfunction "A_2") (pintype "passive"))
      (node (ref "R35") (pin "1") (pinfunction "1_1") (pintype "passive"))
    )
    (net (code "29") (name "Net-(LED4-C)") (class "Default")
      (node (ref "LED4") (pin "1") (pinfunction "C_1") (pintype "passive"))
      (node (ref "Q8") (pin "3") (pinfunction "D_3") (pintype "passive"))
    )
    (net (code "30") (name "Net-(LED5-A)") (class "Default")
      (node (ref "LED5") (pin "2") (pinfunction "A_2") (pintype "passive"))
      (node (ref "R42") (pin "1") (pinfunction "1_1") (pintype "passive"))
    )
    (net (code "31") (name "Net-(LED5-C)") (class "Default")
      (node (ref "LED5") (pin "1") (pinfunction "C_1") (pintype "passive"))
      (node (ref "Q9") (pin "3") (pinfunction "D_3") (pintype "passive"))
    )
    (net (code "32") (name "Net-(LED6-A)") (class "Default")
      (node (ref "LED6") (pin "2") (pinfunction "A_2") (pintype "passive"))
      (node (ref "R43") (pin "1") (pinfunction "1_1") (pintype "passive"))
    )
    (net (code "33") (name "Net-(LED6-C)") (class "Default")
      (node (ref "LED6") (pin "1") (pinfunction "C_1") (pintype "passive"))
      (node (ref "Q10") (pin "3") (pinfunction "D_3") (pintype "passive"))
    )
    (net (code "34") (name "Net-(Q7-G)") (class "Default")
      (node (ref "Q7") (pin "1") (pinfunction "G_1") (pintype "passive"))
      (node (ref "R39") (pin "2") (pinfunction "2_2") (pintype "passive"))
    )
    (net (code "35") (name "Net-(Q8-G)") (class "Default")
      (node (ref "Q8") (pin "1") (pinfunction "G_1") (pintype "passive"))
      (node (ref "R40") (pin "2") (pinfunction "2_2") (pintype "passive"))
    )
    (net (code "36") (name "Net-(Q9-G)") (class "Default")
      (node (ref "Q9") (pin "1") (pinfunction "G_1") (pintype "passive"))
      (node (ref "R47") (pin "2") (pinfunction "2_2") (pintype "passive"))
    )
    (net (code "37") (name "Net-(Q10-G)") (class "Default")
      (node (ref "Q10") (pin "1") (pinfunction "G_1") (pintype "passive"))
      (node (ref "R48") (pin "2") (pinfunction "2_2") (pintype "passive"))
    )
    (net (code "38") (name "Net-(U3-1DIR)") (class "Default")
      (node (ref "R50") (pin "1") (pinfunction "1_1") (pintype "passive"))
      (node (ref "U3") (pin "4") (pinfunction "1DIR_4") (pintype "input"))
      (node (ref "U3") (pin "5") (pinfunction "2DIR_5") (pintype "input"))
    )
    (net (code "39") (name "P3V3") (class "Default")
      (node (ref "C71") (pin "2") (pinfunction "2_2") (pintype "passive"))
      (node (ref "C74") (pin "2") (pinfunction "2_2") (pintype "passive"))
      (node (ref "C77") (pin "2") (pinfunction "2_2") (pintype "passive"))
      (node (ref "C80") (pin "2") (pinfunction "2_2") (pintype "passive"))
      (node (ref "C82") (pin "2") (pinfunction "2_2") (pintype "passive"))
      (node (ref "L2") (pin "2") (pinfunction "2_2") (pintype "passive"))
      (node (ref "L3") (pin "2") (pinfunction "2_2") (pintype "passive"))
      (node (ref "L4") (pin "2") (pinfunction "2_2") (pintype "passive"))
      (node (ref "L5") (pin "2") (pinfunction "2_2") (pintype "passive"))
      (node (ref "U3") (pin "2") (pinfunction "VCCB_2") (pintype "power_in"))
    )
    (net (code "40") (name "VADJ") (class "Default")
      (node (ref "C81") (pin "2") (pinfunction "2_2") (pintype "passive"))
      (node (ref "R50") (pin "2") (pinfunction "2_2") (pintype "passive"))
      (node (ref "U3") (pin "3") (pinfunction "VCCA_3") (pintype "power_in"))
    )
    (net (code "41") (name "VccR0") (class "Default")
      (node (ref "C69") (pin "2") (pinfunction "2_2") (pintype "passive"))
      (node (ref "C70") (pin "2") (pinfunction "2_2") (pintype "passive"))
      (node (ref "J2") (pin "15") (pinfunction "VCCR_15") (pintype "power_in"))
      (node (ref "L2") (pin "1") (pinfunction "1_1") (pintype "passive"))
      (node (ref "R35") (pin "2") (pinfunction "2_2") (pintype "passive"))
      (node (ref "R38") (pin "2") (pinfunction "2_2") (pintype "passive"))
      (node (ref "R41") (pin "2") (pinfunction "2_2") (pintype "passive"))
    )
    (net (code "42") (name "VccR1") (class "Default")
      (node (ref "C75") (pin "2") (pinfunction "2_2") (pintype "passive"))
      (node (ref "C76") (pin "2") (pinfunction "2_2") (pintype "passive"))
      (node (ref "J3") (pin "15") (pinfunction "VCCR_15") (pintype "power_in"))
      (node (ref "L4") (pin "1") (pinfunction "1_1") (pintype "passive"))
      (node (ref "R43") (pin "2") (pinfunction "2_2") (pintype "passive"))
      (node (ref "R46") (pin "2") (pinfunction "2_2") (pintype "passive"))
      (node (ref "R49") (pin "2") (pinfunction "2_2") (pintype "passive"))
    )
    (net (code "43") (name "VccT0") (class "Default")
      (node (ref "C72") (pin "2") (pinfunction "2_2") (pintype "passive"))
      (node (ref "C73") (pin "2") (pinfunction "2_2") (pintype "passive"))
      (node (ref "J2") (pin "16") (pinfunction "VCCT_16") (pintype "power_in"))
      (node (ref "L3") (pin "1") (pinfunction "1_1") (pintype "passive"))
      (node (ref "R34") (pin "2") (pinfunction "2_2") (pintype "passive"))
      (node (ref "R36") (pin "2") (pinfunction "2_2") (pintype "passive"))
      (node (ref "R37") (pin "2") (pinfunction "2_2") (pintype "passive"))
    )
    (net (code "44") (name "VccT1") (class "Default")
      (node (ref "C78") (pin "2") (pinfunction "2_2") (pintype "passive"))
      (node (ref "C79") (pin "2") (pinfunction "2_2") (pintype "passive"))
      (node (ref "J3") (pin "16") (pinfunction "VCCT_16") (pintype "power_in"))
      (node (ref "L5") (pin "1") (pinfunction "1_1") (pintype "passive"))
      (node (ref "R42") (pin "2") (pinfunction "2_2") (pintype "passive"))
      (node (ref "R44") (pin "2") (pinfunction "2_2") (pintype "passive"))
      (node (ref "R45") (pin "2") (pinfunction "2_2") (pintype "passive"))
    )
    (net (code "45") (name "unconnected-(J2-RS0-Pad7)") (class "Default")
      (node (ref "J2") (pin "7") (pinfunction "RS0_7") (pintype "input+no_connect"))
    )
    (net (code "46") (name "unconnected-(J2-RS1-Pad9)") (class "Default")
      (node (ref "J2") (pin "9") (pinfunction "RS1_9") (pintype "input+no_connect"))
    )
    (net (code "47") (name "unconnected-(J3-RS0-Pad7)") (class "Default")
      (node (ref "J3") (pin "7") (pinfunction "RS0_7") (pintype "input+no_connect"))
    )
    (net (code "48") (name "unconnected-(J3-RS1-Pad9)") (class "Default")
      (node (ref "J3") (pin "9") (pinfunction "RS1_9") (pintype "input+no_connect"))
    )
  )
)
